# DMX-Switch.net
KiCad netlist of a schematic drawn in EAGLE
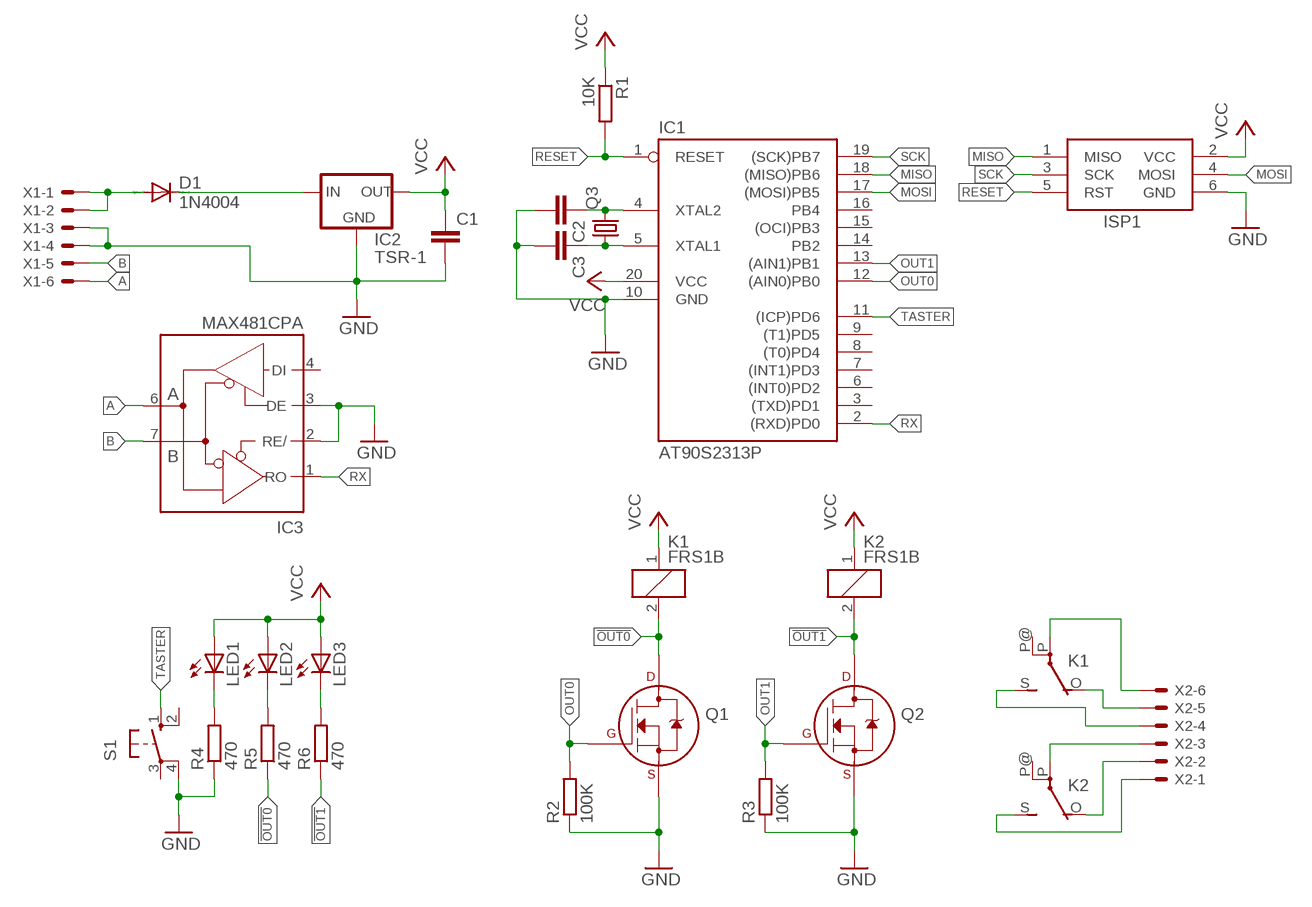
[diagram p0: schematic, sheet 1]

(export (version "E")
  (design (tool "Eeschema 10.0.6"))
  (components
    (comp (ref "C1")
      (value "C-EU025-024X044")
      (footprint "eagle-import:C025-024X044")
      (libsource (lib "eagle-import") (part "C-EU025-024X044"))
    )
    (comp (ref "C2")
      (value "C-EU025-024X044")
      (footprint "eagle-import:C025-024X044")
      (libsource (lib "eagle-import") (part "C-EU025-024X044"))
    )
    (comp (ref "C3")
      (value "C-EU025-024X044")
      (footprint "eagle-import:C025-024X044")
      (libsource (lib "eagle-import") (part "C-EU025-024X044"))
    )
    (comp (ref "D1")
      (value "1N4004")
      (footprint "eagle-import:DO41-10")
      (libsource (lib "eagle-import") (part "1N4004"))
    )
    (comp (ref "IC1")
      (value "AT90S2313P")
      (footprint "eagle-import:DIL20")
      (libsource (lib "eagle-import") (part "AT90S2313P"))
    )
    (comp (ref "IC2")
      (value "TSR-1")
      (footprint "eagle-import:TSR-1")
      (libsource (lib "eagle-import") (part "TSR-1"))
    )
    (comp (ref "IC3")
      (value "MAX481CPA")
      (footprint "eagle-import:DIL08")
      (fields (field (name "MPN") "MAX481CPA+"))
      (libsource (lib "eagle-import") (part "MAX481CPA"))
    )
    (comp (ref "ISP1")
      (value "AVRISP-BOX")
      (footprint "eagle-import:AVRISP-BOX")
      (libsource (lib "eagle-import") (part "AVRISP-BOX"))
    )
    (comp (ref "K1")
      (value "FRS1B")
      (footprint "eagle-import:FRS1B")
      (libsource (lib "eagle-import") (part "FRS1B"))
    )
    (comp (ref "K2")
      (value "FRS1B")
      (footprint "eagle-import:FRS1B")
      (libsource (lib "eagle-import") (part "FRS1B"))
    )
    (comp (ref "LED1")
      (value "LED5MM")
      (footprint "eagle-import:LED5MM")
      (libsource (lib "eagle-import") (part "LED5MM"))
    )
    (comp (ref "LED2")
      (value "LED5MM")
      (footprint "eagle-import:LED5MM")
      (libsource (lib "eagle-import") (part "LED5MM"))
    )
    (comp (ref "LED3")
      (value "LED5MM")
      (footprint "eagle-import:LED5MM")
      (libsource (lib "eagle-import") (part "LED5MM"))
    )
    (comp (ref "Q1")
      (value "2N7000_TO92")
      (footprint "eagle-import:TO-92")
      (libsource (lib "eagle-import") (part "2N700_TO920"))
    )
    (comp (ref "Q2")
      (value "2N7000_TO92")
      (footprint "eagle-import:TO-92")
      (libsource (lib "eagle-import") (part "2N700_TO920"))
    )
    (comp (ref "Q3")
      (value "CRYSTALHC49S")
      (footprint "eagle-import:HC49_S")
      (libsource (lib "eagle-import") (part "CRYSTALHC49S"))
    )
    (comp (ref "R1")
      (value "10K")
      (footprint "eagle-import:0204_7")
      (libsource (lib "eagle-import") (part "R-EU_0204/7"))
    )
    (comp (ref "R2")
      (value "100K")
      (footprint "eagle-import:0204_7")
      (libsource (lib "eagle-import") (part "R-EU_0204/7"))
    )
    (comp (ref "R3")
      (value "100K")
      (footprint "eagle-import:0204_7")
      (libsource (lib "eagle-import") (part "R-EU_0204/7"))
    )
    (comp (ref "R4")
      (value "470")
      (footprint "eagle-import:0204_7")
      (libsource (lib "eagle-import") (part "R-EU_0204/7"))
    )
    (comp (ref "R5")
      (value "470")
      (footprint "eagle-import:0204_7")
      (libsource (lib "eagle-import") (part "R-EU_0204/7"))
    )
    (comp (ref "R6")
      (value "470")
      (footprint "eagle-import:0204_7")
      (libsource (lib "eagle-import") (part "R-EU_0204/7"))
    )
    (comp (ref "S1")
      (value "10-XX")
      (footprint "eagle-import:B3F-10XX")
      (fields (field (name "MPN") "B3F-1000"))
      (libsource (lib "eagle-import") (part "10-XX"))
    )
    (comp (ref "X1")
      (value "KK-156-6")
      (footprint "eagle-import:KK-156-6")
      (libsource (lib "eagle-import") (part "KK-156-6"))
    )
    (comp (ref "X2")
      (value "KK-156-6")
      (footprint "eagle-import:KK-156-6")
      (libsource (lib "eagle-import") (part "KK-156-6"))
    )
  )
  (nets
    (net (code "1") (name "/~{OUT0}") (class "Default")
      (node (ref "K1") (pin "2") (pinfunction "2_2") (pintype "passive"))
      (node (ref "Q1") (pin "3") (pinfunction "D_3") (pintype "bidirectional"))
      (node (ref "R5") (pin "1") (pinfunction "1_1") (pintype "passive"))
    )
    (net (code "2") (name "/~{OUT1}") (class "Default")
      (node (ref "K2") (pin "2") (pinfunction "2_2") (pintype "passive"))
      (node (ref "Q2") (pin "3") (pinfunction "D_3") (pintype "bidirectional"))
      (node (ref "R6") (pin "1") (pinfunction "1_1") (pintype "passive"))
    )
    (net (code "3") (name "A") (class "Default")
      (node (ref "IC3") (pin "6") (pinfunction "A_6") (pintype "passive"))
      (node (ref "X1") (pin "6") (pinfunction "S_6") (pintype "passive"))
    )
    (net (code "4") (name "B") (class "Default")
      (node (ref "IC3") (pin "7") (pinfunction "B_7") (pintype "passive"))
      (node (ref "X1") (pin "5") (pinfunction "S_5") (pintype "passive"))
    )
    (net (code "5") (name "GND") (class "Default")
      (node (ref "C1") (pin "2") (pinfunction "2_2") (pintype "passive"))
      (node (ref "C2") (pin "2") (pinfunction "2_2") (pintype "passive"))
      (node (ref "C3") (pin "2") (pinfunction "2_2") (pintype "passive"))
      (node (ref "IC1") (pin "10") (pinfunction "GND_10") (pintype "power_in"))
      (node (ref "IC2") (pin "2") (pinfunction "GND_2") (pintype "input"))
      (node (ref "IC3") (pin "2") (pinfunction "RE/_2") (pintype "input"))
      (node (ref "IC3") (pin "3") (pinfunction "DE_3") (pintype "input"))
      (node (ref "ISP1") (pin "6") (pinfunction "GND_6") (pintype "power_in"))
      (node (ref "Q1") (pin "1") (pinfunction "S_1") (pintype "bidirectional"))
      (node (ref "Q2") (pin "1") (pinfunction "S_1") (pintype "bidirectional"))
      (node (ref "R2") (pin "1") (pinfunction "1_1") (pintype "passive"))
      (node (ref "R3") (pin "1") (pinfunction "1_1") (pintype "passive"))
      (node (ref "R4") (pin "1") (pinfunction "1_1") (pintype "passive"))
      (node (ref "S1") (pin "4") (pinfunction "P1_4") (pintype "passive"))
      (node (ref "X1") (pin "3") (pinfunction "S_3") (pintype "passive"))
      (node (ref "X1") (pin "4") (pinfunction "S_4") (pintype "passive"))
    )
    (net (code "6") (name "MISO") (class "Default")
      (node (ref "IC1") (pin "18") (pinfunction "(MISO)PB6_18") (pintype "bidirectional"))
      (node (ref "ISP1") (pin "1") (pinfunction "MISO_1") (pintype "input"))
    )
    (net (code "7") (name "MOSI") (class "Default")
      (node (ref "IC1") (pin "17") (pinfunction "(MOSI)PB5_17") (pintype "bidirectional"))
      (node (ref "ISP1") (pin "4") (pinfunction "MOSI_4") (pintype "output"))
    )
    (net (code "8") (name "Net-(IC1-XTAL1)") (class "Default")
      (node (ref "C3") (pin "1") (pinfunction "1_1") (pintype "passive"))
      (node (ref "IC1") (pin "5") (pinfunction "XTAL1_5") (pintype "bidirectional"))
      (node (ref "Q3") (pin "1") (pinfunction "1_1") (pintype "passive"))
    )
    (net (code "9") (name "Net-(IC1-XTAL2)") (class "Default")
      (node (ref "C2") (pin "1") (pinfunction "1_1") (pintype "passive"))
      (node (ref "IC1") (pin "4") (pinfunction "XTAL2_4") (pintype "bidirectional"))
      (node (ref "Q3") (pin "2") (pinfunction "2_2") (pintype "passive"))
    )
    (net (code "10") (name "Net-(IC2-IN)") (class "Default")
      (node (ref "D1") (pin "C") (pinfunction "C_C") (pintype "passive"))
      (node (ref "IC2") (pin "1") (pinfunction "IN_1") (pintype "input"))
    )
    (net (code "11") (name "Net-(LED1-C)") (class "Default")
      (node (ref "LED1") (pin "K") (pinfunction "C_K") (pintype "passive"))
      (node (ref "R4") (pin "2") (pinfunction "2_2") (pintype "passive"))
    )
    (net (code "12") (name "Net-(LED2-C)") (class "Default")
      (node (ref "LED2") (pin "K") (pinfunction "C_K") (pintype "passive"))
      (node (ref "R5") (pin "2") (pinfunction "2_2") (pintype "passive"))
    )
    (net (code "13") (name "Net-(LED3-C)") (class "Default")
      (node (ref "LED3") (pin "K") (pinfunction "C_K") (pintype "passive"))
      (node (ref "R6") (pin "2") (pinfunction "2_2") (pintype "passive"))
    )
    (net (code "14") (name "Net-(X1A-S)") (class "Default")
      (node (ref "D1") (pin "A") (pinfunction "A_A") (pintype "passive"))
      (node (ref "X1") (pin "1") (pinfunction "S_1") (pintype "passive"))
      (node (ref "X1") (pin "2") (pinfunction "S_2") (pintype "passive"))
    )
    (net (code "15") (name "Net-(X2A-S)") (class "Default")
      (node (ref "K2") (pin "S") (pinfunction "S_S") (pintype "passive"))
      (node (ref "X2") (pin "1") (pinfunction "S_1") (pintype "passive"))
    )
    (net (code "16") (name "Net-(X2B-S)") (class "Default")
      (node (ref "K2") (pin "O") (pinfunction "O_O") (pintype "passive"))
      (node (ref "X2") (pin "2") (pinfunction "S_2") (pintype "passive"))
    )
    (net (code "17") (name "Net-(X2C-S)") (class "Default")
      (node (ref "K2") (pin "P") (pinfunction "P_P") (pintype "passive"))
      (node (ref "X2") (pin "3") (pinfunction "S_3") (pintype "passive"))
    )
    (net (code "18") (name "Net-(X2D-S)") (class "Default")
      (node (ref "K1") (pin "S") (pinfunction "S_S") (pintype "passive"))
      (node (ref "X2") (pin "4") (pinfunction "S_4") (pintype "passive"))
    )
    (net (code "19") (name "Net-(X2E-S)") (class "Default")
      (node (ref "K1") (pin "O") (pinfunction "O_O") (pintype "passive"))
      (node (ref "X2") (pin "5") (pinfunction "S_5") (pintype "passive"))
    )
    (net (code "20") (name "Net-(X2F-S)") (class "Default")
      (node (ref "K1") (pin "P") (pinfunction "P_P") (pintype "passive"))
      (node (ref "X2") (pin "6") (pinfunction "S_6") (pintype "passive"))
    )
    (net (code "21") (name "OUT0") (class "Default")
      (node (ref "IC1") (pin "12") (pinfunction "(AIN0)PB0_12") (pintype "bidirectional"))
      (node (ref "Q1") (pin "2") (pinfunction "G_2") (pintype "tri_state"))
      (node (ref "R2") (pin "2") (pinfunction "2_2") (pintype "passive"))
    )
    (net (code "22") (name "OUT1") (class "Default")
      (node (ref "IC1") (pin "13") (pinfunction "(AIN1)PB1_13") (pintype "bidirectional"))
      (node (ref "Q2") (pin "2") (pinfunction "G_2") (pintype "tri_state"))
      (node (ref "R3") (pin "2") (pinfunction "2_2") (pintype "passive"))
    )
    (net (code "23") (name "RESET") (class "Default")
      (node (ref "IC1") (pin "1") (pinfunction "RESET_1") (pintype "bidirectional"))
      (node (ref "ISP1") (pin "5") (pinfunction "RST_5") (pintype "output"))
      (node (ref "R1") (pin "2") (pinfunction "2_2") (pintype "passive"))
    )
    (net (code "24") (name "RX") (class "Default")
      (node (ref "IC1") (pin "2") (pinfunction "(RXD)PD0_2") (pintype "bidirectional"))
      (node (ref "IC3") (pin "1") (pinfunction "RO_1") (pintype "output"))
    )
    (net (code "25") (name "SCK") (class "Default")
      (node (ref "IC1") (pin "19") (pinfunction "(SCK)PB7_19") (pintype "bidirectional"))
      (node (ref "ISP1") (pin "3") (pinfunction "SCK_3") (pintype "output"))
    )
    (net (code "26") (name "TASTER") (class "Default")
      (node (ref "IC1") (pin "11") (pinfunction "(ICP)PD6_11") (pintype "bidirectional"))
      (node (ref "S1") (pin "1") (pinfunction "S_1") (pintype "passive"))
    )
    (net (code "27") (name "VCC") (class "Default")
      (node (ref "C1") (pin "1") (pinfunction "1_1") (pintype "passive"))
      (node (ref "IC1") (pin "20") (pinfunction "VCC_20") (pintype "power_in"))
      (node (ref "IC2") (pin "3") (pinfunction "OUT_3") (pintype "passive"))
      (node (ref "ISP1") (pin "2") (pinfunction "VCC_2") (pintype "power_in"))
      (node (ref "K1") (pin "1") (pinfunction "1_1") (pintype "passive"))
      (node (ref "K2") (pin "1") (pinfunction "1_1") (pintype "passive"))
      (node (ref "LED1") (pin "A") (pinfunction "A_A") (pintype "passive"))
      (node (ref "LED2") (pin "A") (pinfunction "A_A") (pintype "passive"))
      (node (ref "LED3") (pin "A") (pinfunction "A_A") (pintype "passive"))
      (node (ref "R1") (pin "1") (pinfunction "1_1") (pintype "passive"))
    )
    (net (code "28") (name "unconnected-(IC1-(INT0)PD2-Pad6)") (class "Default")
      (node (ref "IC1") (pin "6") (pinfunction "(INT0)PD2_6") (pintype "bidirectional"))
    )
    (net (code "29") (name "unconnected-(IC1-(INT1)PD3-Pad7)") (class "Default")
      (node (ref "IC1") (pin "7") (pinfunction "(INT1)PD3_7") (pintype "bidirectional"))
    )
    (net (code "30") (name "unconnected-(IC1-(OCI)PB3-Pad15)") (class "Default")
      (node (ref "IC1") (pin "15") (pinfunction "(OCI)PB3_15") (pintype "bidirectional"))
    )
    (net (code "31") (name "unconnected-(IC1-(T0)PD4-Pad8)") (class "Default")
      (node (ref "IC1") (pin "8") (pinfunction "(T0)PD4_8") (pintype "bidirectional"))
    )
    (net (code "32") (name "unconnected-(IC1-(T1)PD5-Pad9)") (class "Default")
      (node (ref "IC1") (pin "9") (pinfunction "(T1)PD5_9") (pintype "bidirectional"))
    )
    (net (code "33") (name "unconnected-(IC1-(TXD)PD1-Pad3)") (class "Default")
      (node (ref "IC1") (pin "3") (pinfunction "(TXD)PD1_3") (pintype "bidirectional"))
    )
    (net (code "34") (name "unconnected-(IC1-PB2-Pad14)") (class "Default")
      (node (ref "IC1") (pin "14") (pinfunction "PB2_14") (pintype "bidirectional"))
    )
    (net (code "35") (name "unconnected-(IC1-PB4-Pad16)") (class "Default")
      (node (ref "IC1") (pin "16") (pinfunction "PB4_16") (pintype "bidirectional"))
    )
    (net (code "36") (name "unconnected-(IC3A-DI-Pad4)") (class "Default")
      (node (ref "IC3") (pin "4") (pinfunction "DI_4") (pintype "input"))
    )
    (net (code "37") (name "unconnected-(K1B-P-PadP@)") (class "Default")
      (node (ref "K1") (pin "P@") (pinfunction "P_P@") (pintype "passive"))
    )
    (net (code "38") (name "unconnected-(K2B-P-PadP@)") (class "Default")
      (node (ref "K2") (pin "P@") (pinfunction "P_P@") (pintype "passive"))
    )
    (net (code "39") (name "unconnected-(S1-P-Pad3)") (class "Default")
      (node (ref "S1") (pin "3") (pinfunction "P_3") (pintype "passive"))
    )
    (net (code "40") (name "unconnected-(S1-S1-Pad2)") (class "Default")
      (node (ref "S1") (pin "2") (pinfunction "S1_2") (pintype "passive"))
    )
  )
)
